# ArduSensor_Shield-v13.net
KiCad netlist of a schematic drawn in EAGLE
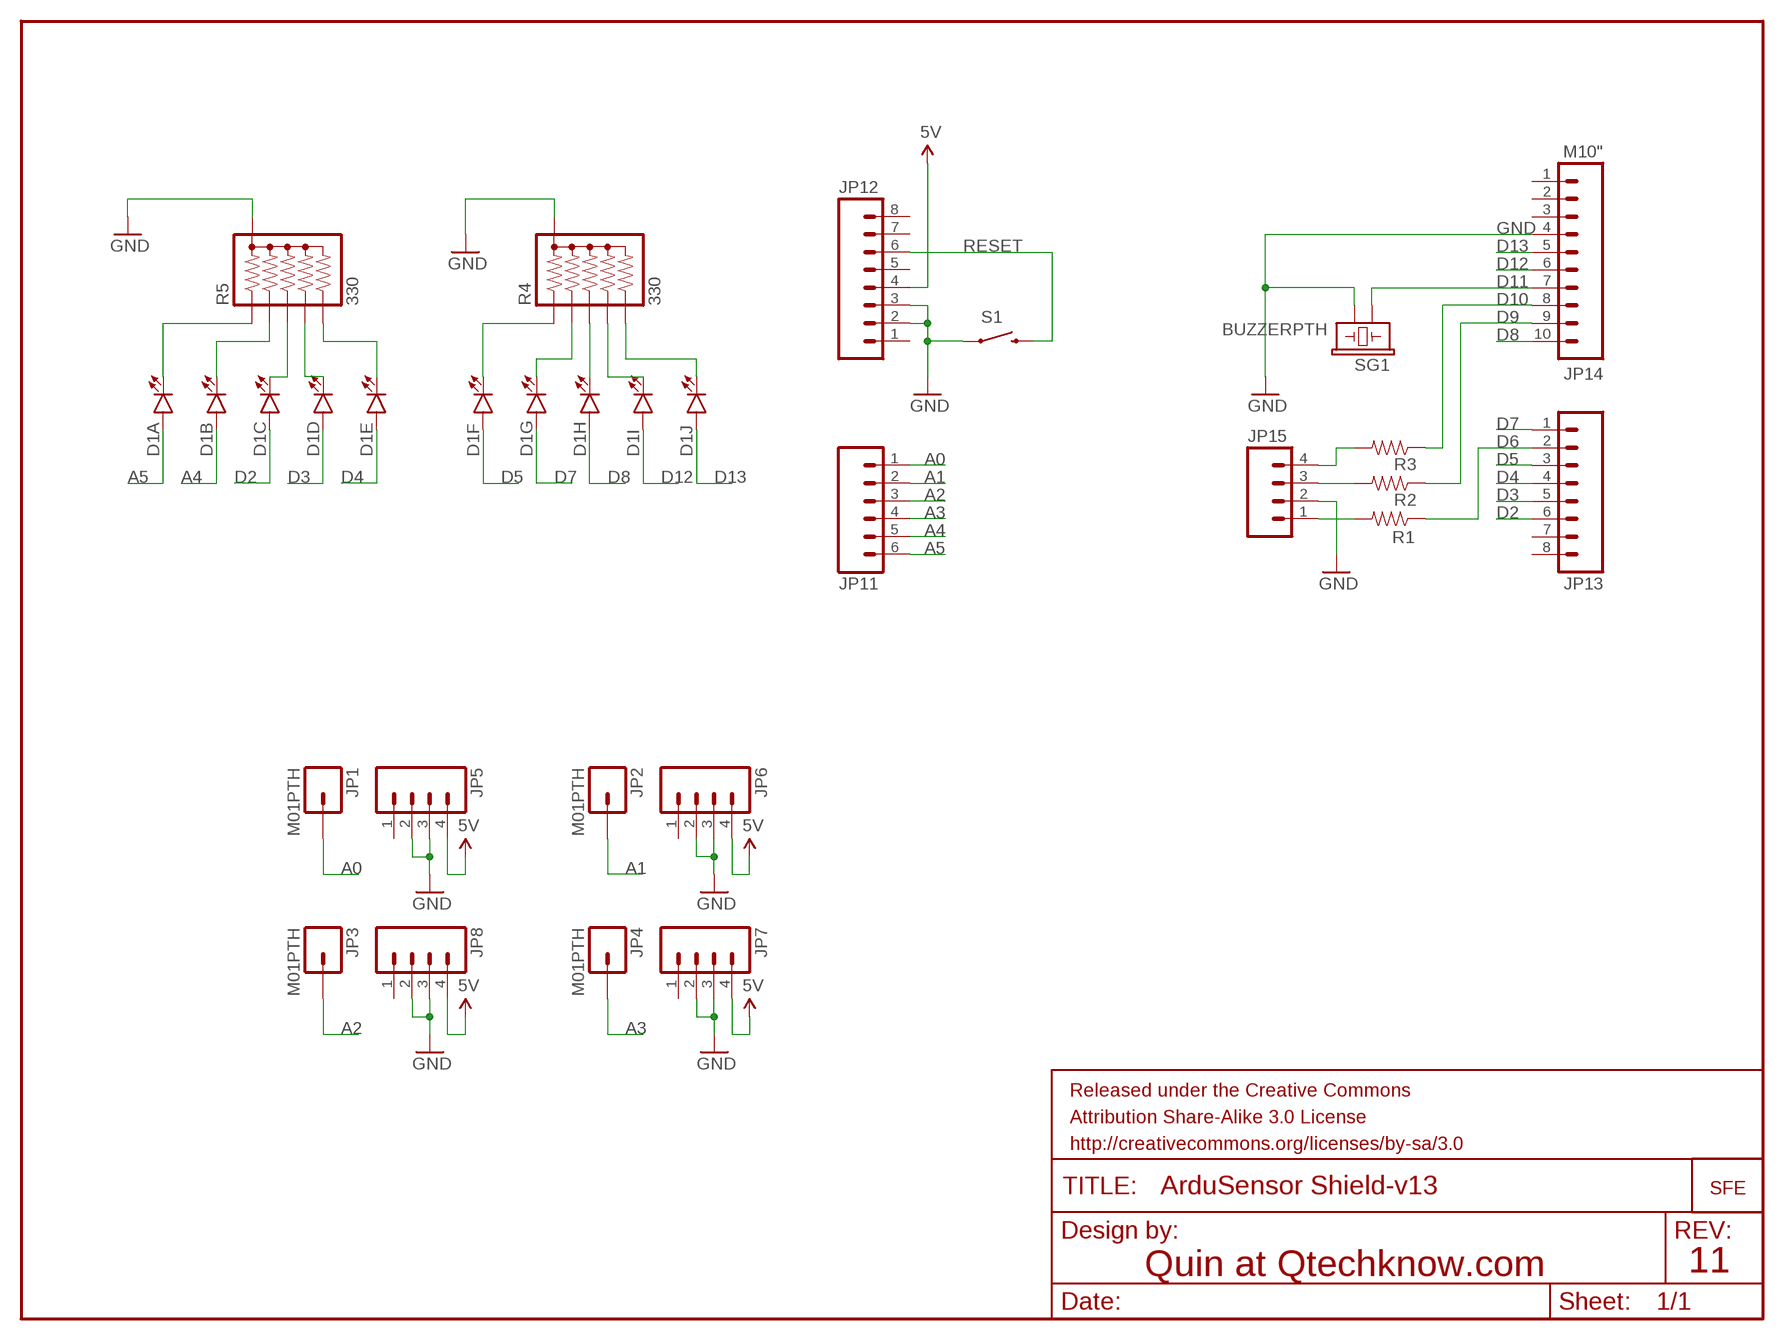
[diagram p0: schematic, sheet 1]

(export (version "E")
  (design (tool "Eeschema 10.0.6"))
  (components
    (comp (ref "D1")
      (value "LED_BARGRAPH_10")
      (footprint "eagle-import:LED_BARGAPH_10")
      (libsource (lib "eagle-import") (part "LED_BARGRAPH_10"))
    )
    (comp (ref "FRAME1")
      (value "FRAME-LETTER")
      (footprint "eagle-import:CREATIVE_COMMONS")
      (libsource (lib "eagle-import") (part "FRAME-LETTER"))
    )
    (comp (ref "JP1")
      (value "M01PTH")
      (footprint "eagle-import:1X01")
      (libsource (lib "eagle-import") (part "M01PTH"))
    )
    (comp (ref "JP2")
      (value "M01PTH")
      (footprint "eagle-import:1X01")
      (libsource (lib "eagle-import") (part "M01PTH"))
    )
    (comp (ref "JP3")
      (value "M01PTH")
      (footprint "eagle-import:1X01")
      (libsource (lib "eagle-import") (part "M01PTH"))
    )
    (comp (ref "JP4")
      (value "M01PTH")
      (footprint "eagle-import:1X01")
      (libsource (lib "eagle-import") (part "M01PTH"))
    )
    (comp (ref "JP5")
      (value "M04PTH")
      (footprint "eagle-import:1X04")
      (libsource (lib "eagle-import") (part "M04PTH"))
    )
    (comp (ref "JP6")
      (value "M04PTH")
      (footprint "eagle-import:1X04")
      (libsource (lib "eagle-import") (part "M04PTH"))
    )
    (comp (ref "JP7")
      (value "M04PTH")
      (footprint "eagle-import:1X04")
      (libsource (lib "eagle-import") (part "M04PTH"))
    )
    (comp (ref "JP8")
      (value "M04PTH")
      (footprint "eagle-import:1X04")
      (libsource (lib "eagle-import") (part "M04PTH"))
    )
    (comp (ref "JP9")
      (value "LOGO-SFENEW")
      (footprint "eagle-import:SFE-NEW-WEBLOGO")
      (libsource (lib "eagle-import") (part "LOGO-SFENEW"))
    )
    (comp (ref "JP11")
      (value "M06SIP")
      (footprint "eagle-import:1X06")
      (libsource (lib "eagle-import") (part "M06SIP"))
    )
    (comp (ref "JP12")
      (value "M081X08")
      (footprint "eagle-import:1X08")
      (libsource (lib "eagle-import") (part "M081X08"))
    )
    (comp (ref "JP13")
      (value "M081X08")
      (footprint "eagle-import:1X08")
      (libsource (lib "eagle-import") (part "M081X08"))
    )
    (comp (ref "JP14")
      (value "M10\"")
      (footprint "eagle-import:1X10")
      (libsource (lib "eagle-import") (part "M10{dblquote}"))
    )
    (comp (ref "JP15")
      (value "M04PTH")
      (footprint "eagle-import:1X04")
      (libsource (lib "eagle-import") (part "M04PTH"))
    )
    (comp (ref "R1")
      (value "RESISTORPTH-1/6W")
      (footprint "eagle-import:1_6W-RES")
      (libsource (lib "eagle-import") (part "RESISTORPTH-1/6W"))
    )
    (comp (ref "R2")
      (value "RESISTORPTH-1/6W")
      (footprint "eagle-import:1_6W-RES")
      (libsource (lib "eagle-import") (part "RESISTORPTH-1/6W"))
    )
    (comp (ref "R3")
      (value "RESISTORPTH-1/6W")
      (footprint "eagle-import:1_6W-RES")
      (libsource (lib "eagle-import") (part "RESISTORPTH-1/6W"))
    )
    (comp (ref "R4")
      (value "330")
      (footprint "eagle-import:RPACK-SIP-PTH-5")
      (libsource (lib "eagle-import") (part "RPACK-BUSSED-SIP-PTH-5"))
    )
    (comp (ref "R5")
      (value "330")
      (footprint "eagle-import:RPACK-SIP-PTH-5")
      (libsource (lib "eagle-import") (part "RPACK-BUSSED-SIP-PTH-5"))
    )
    (comp (ref "S1")
      (value "SWITCH-MOMENTARY-2PTH")
      (footprint "eagle-import:TACTILE-PTH")
      (libsource (lib "eagle-import") (part "SWITCH-MOMENTARY-2PTH"))
    )
    (comp (ref "SG1")
      (value "BUZZERPTH")
      (footprint "eagle-import:BUZZER-12MM")
      (libsource (lib "eagle-import") (part "BUZZERPTH"))
    )
  )
  (nets
    (net (code "1") (name "/A0") (class "Default")
      (node (ref "JP1") (pin "1") (pinfunction "1_1") (pintype "passive"))
      (node (ref "JP11") (pin "1") (pinfunction "1_1") (pintype "passive"))
    )
    (net (code "2") (name "/A1") (class "Default")
      (node (ref "JP11") (pin "2") (pinfunction "2_2") (pintype "passive"))
      (node (ref "JP2") (pin "1") (pinfunction "1_1") (pintype "passive"))
    )
    (net (code "3") (name "/A2") (class "Default")
      (node (ref "JP11") (pin "3") (pinfunction "3_3") (pintype "passive"))
      (node (ref "JP3") (pin "1") (pinfunction "1_1") (pintype "passive"))
    )
    (net (code "4") (name "/A3") (class "Default")
      (node (ref "JP11") (pin "4") (pinfunction "4_4") (pintype "passive"))
      (node (ref "JP4") (pin "1") (pinfunction "1_1") (pintype "passive"))
    )
    (net (code "5") (name "/A4") (class "Default")
      (node (ref "D1") (pin "2") (pinfunction "A_2") (pintype "passive"))
      (node (ref "JP11") (pin "5") (pinfunction "5_5") (pintype "passive"))
    )
    (net (code "6") (name "/A5") (class "Default")
      (node (ref "D1") (pin "1") (pinfunction "A_1") (pintype "passive"))
      (node (ref "JP11") (pin "6") (pinfunction "6_6") (pintype "passive"))
    )
    (net (code "7") (name "/D2") (class "Default")
      (node (ref "D1") (pin "3") (pinfunction "A_3") (pintype "passive"))
      (node (ref "JP13") (pin "6") (pinfunction "6_6") (pintype "passive"))
    )
    (net (code "8") (name "/D3") (class "Default")
      (node (ref "D1") (pin "4") (pinfunction "A_4") (pintype "passive"))
      (node (ref "JP13") (pin "5") (pinfunction "5_5") (pintype "passive"))
    )
    (net (code "9") (name "/D4") (class "Default")
      (node (ref "D1") (pin "5") (pinfunction "A_5") (pintype "passive"))
      (node (ref "JP13") (pin "4") (pinfunction "4_4") (pintype "passive"))
    )
    (net (code "10") (name "/D5") (class "Default")
      (node (ref "D1") (pin "6") (pinfunction "A_6") (pintype "passive"))
      (node (ref "JP13") (pin "3") (pinfunction "3_3") (pintype "passive"))
    )
    (net (code "11") (name "/D6") (class "Default")
      (node (ref "JP13") (pin "2") (pinfunction "2_2") (pintype "passive"))
      (node (ref "R1") (pin "1") (pinfunction "1_1") (pintype "passive"))
    )
    (net (code "12") (name "/D7") (class "Default")
      (node (ref "D1") (pin "7") (pinfunction "A_7") (pintype "passive"))
      (node (ref "JP13") (pin "1") (pinfunction "1_1") (pintype "passive"))
    )
    (net (code "13") (name "/D8") (class "Default")
      (node (ref "D1") (pin "8") (pinfunction "A_8") (pintype "passive"))
      (node (ref "JP14") (pin "10") (pinfunction "10_10") (pintype "passive"))
    )
    (net (code "14") (name "/D9") (class "Default")
      (node (ref "JP14") (pin "9") (pinfunction "9_9") (pintype "passive"))
      (node (ref "R2") (pin "1") (pinfunction "1_1") (pintype "passive"))
    )
    (net (code "15") (name "/D10") (class "Default")
      (node (ref "JP14") (pin "8") (pinfunction "8_8") (pintype "passive"))
      (node (ref "R3") (pin "1") (pinfunction "1_1") (pintype "passive"))
    )
    (net (code "16") (name "/D11") (class "Default")
      (node (ref "JP14") (pin "7") (pinfunction "7_7") (pintype "passive"))
      (node (ref "SG1") (pin "+") (pinfunction "1_+") (pintype "passive"))
    )
    (net (code "17") (name "/D12") (class "Default")
      (node (ref "D1") (pin "9") (pinfunction "A_9") (pintype "passive"))
      (node (ref "JP14") (pin "6") (pinfunction "6_6") (pintype "passive"))
    )
    (net (code "18") (name "/D13") (class "Default")
      (node (ref "D1") (pin "10") (pinfunction "A_10") (pintype "passive"))
      (node (ref "JP14") (pin "5") (pinfunction "5_5") (pintype "passive"))
    )
    (net (code "19") (name "/RESET") (class "Default")
      (node (ref "JP12") (pin "6") (pinfunction "6_6") (pintype "passive"))
      (node (ref "S1") (pin "3") (pinfunction "2_3") (pintype "passive"))
    )
    (net (code "20") (name "5V") (class "Default")
      (node (ref "JP12") (pin "4") (pinfunction "4_4") (pintype "passive"))
      (node (ref "JP5") (pin "4") (pinfunction "4_4") (pintype "passive"))
      (node (ref "JP6") (pin "4") (pinfunction "4_4") (pintype "passive"))
      (node (ref "JP7") (pin "4") (pinfunction "4_4") (pintype "passive"))
      (node (ref "JP8") (pin "4") (pinfunction "4_4") (pintype "passive"))
    )
    (net (code "21") (name "GND") (class "Default")
      (node (ref "JP12") (pin "2") (pinfunction "2_2") (pintype "passive"))
      (node (ref "JP12") (pin "3") (pinfunction "3_3") (pintype "passive"))
      (node (ref "JP14") (pin "4") (pinfunction "4_4") (pintype "passive"))
      (node (ref "JP15") (pin "2") (pinfunction "2_2") (pintype "passive"))
      (node (ref "JP5") (pin "2") (pinfunction "2_2") (pintype "passive"))
      (node (ref "JP5") (pin "3") (pinfunction "3_3") (pintype "passive"))
      (node (ref "JP6") (pin "2") (pinfunction "2_2") (pintype "passive"))
      (node (ref "JP6") (pin "3") (pinfunction "3_3") (pintype "passive"))
      (node (ref "JP7") (pin "2") (pinfunction "2_2") (pintype "passive"))
      (node (ref "JP7") (pin "3") (pinfunction "3_3") (pintype "passive"))
      (node (ref "JP8") (pin "2") (pinfunction "2_2") (pintype "passive"))
      (node (ref "JP8") (pin "3") (pinfunction "3_3") (pintype "passive"))
      (node (ref "R4") (pin "P$1") (pinfunction "1_P$1") (pintype "passive"))
      (node (ref "R5") (pin "P$1") (pinfunction "1_P$1") (pintype "passive"))
      (node (ref "S1") (pin "1") (pinfunction "1_1") (pintype "passive"))
      (node (ref "SG1") (pin "-") (pinfunction "2_-") (pintype "passive"))
    )
    (net (code "22") (name "Net-(D1A-C)") (class "Default")
      (node (ref "D1") (pin "20") (pinfunction "C_20") (pintype "passive"))
      (node (ref "R5") (pin "P$2") (pinfunction "2_P$2") (pintype "passive"))
    )
    (net (code "23") (name "Net-(D1B-C)") (class "Default")
      (node (ref "D1") (pin "19") (pinfunction "C_19") (pintype "passive"))
      (node (ref "R5") (pin "P$3") (pinfunction "3_P$3") (pintype "passive"))
    )
    (net (code "24") (name "Net-(D1C-C)") (class "Default")
      (node (ref "D1") (pin "18") (pinfunction "C_18") (pintype "passive"))
      (node (ref "R5") (pin "P$4") (pinfunction "4_P$4") (pintype "passive"))
    )
    (net (code "25") (name "Net-(D1D-C)") (class "Default")
      (node (ref "D1") (pin "17") (pinfunction "C_17") (pintype "passive"))
      (node (ref "R5") (pin "P$5") (pinfunction "5_P$5") (pintype "passive"))
    )
    (net (code "26") (name "Net-(D1E-C)") (class "Default")
      (node (ref "D1") (pin "16") (pinfunction "C_16") (pintype "passive"))
      (node (ref "R5") (pin "P$6") (pinfunction "6_P$6") (pintype "passive"))
    )
    (net (code "27") (name "Net-(D1F-C)") (class "Default")
      (node (ref "D1") (pin "15") (pinfunction "C_15") (pintype "passive"))
      (node (ref "R4") (pin "P$2") (pinfunction "2_P$2") (pintype "passive"))
    )
    (net (code "28") (name "Net-(D1G-C)") (class "Default")
      (node (ref "D1") (pin "14") (pinfunction "C_14") (pintype "passive"))
      (node (ref "R4") (pin "P$3") (pinfunction "3_P$3") (pintype "passive"))
    )
    (net (code "29") (name "Net-(D1H-C)") (class "Default")
      (node (ref "D1") (pin "13") (pinfunction "C_13") (pintype "passive"))
      (node (ref "R4") (pin "P$4") (pinfunction "4_P$4") (pintype "passive"))
    )
    (net (code "30") (name "Net-(D1I-C)") (class "Default")
      (node (ref "D1") (pin "12") (pinfunction "C_12") (pintype "passive"))
      (node (ref "R4") (pin "P$5") (pinfunction "5_P$5") (pintype "passive"))
    )
    (net (code "31") (name "Net-(D1J-C)") (class "Default")
      (node (ref "D1") (pin "11") (pinfunction "C_11") (pintype "passive"))
      (node (ref "R4") (pin "P$6") (pinfunction "6_P$6") (pintype "passive"))
    )
    (net (code "32") (name "Net-(JP15-Pad1)") (class "Default")
      (node (ref "JP15") (pin "1") (pinfunction "1_1") (pintype "passive"))
      (node (ref "R1") (pin "2") (pinfunction "2_2") (pintype "passive"))
    )
    (net (code "33") (name "Net-(JP15-Pad3)") (class "Default")
      (node (ref "JP15") (pin "3") (pinfunction "3_3") (pintype "passive"))
      (node (ref "R2") (pin "2") (pinfunction "2_2") (pintype "passive"))
    )
    (net (code "34") (name "Net-(JP15-Pad4)") (class "Default")
      (node (ref "JP15") (pin "4") (pinfunction "4_4") (pintype "passive"))
      (node (ref "R3") (pin "2") (pinfunction "2_2") (pintype "passive"))
    )
    (net (code "35") (name "unconnected-(JP5-Pad1)") (class "Default")
      (node (ref "JP5") (pin "1") (pinfunction "1_1") (pintype "passive"))
    )
    (net (code "36") (name "unconnected-(JP6-Pad1)") (class "Default")
      (node (ref "JP6") (pin "1") (pinfunction "1_1") (pintype "passive"))
    )
    (net (code "37") (name "unconnected-(JP7-Pad1)") (class "Default")
      (node (ref "JP7") (pin "1") (pinfunction "1_1") (pintype "passive"))
    )
    (net (code "38") (name "unconnected-(JP8-Pad1)") (class "Default")
      (node (ref "JP8") (pin "1") (pinfunction "1_1") (pintype "passive"))
    )
    (net (code "39") (name "unconnected-(JP12-Pad1)") (class "Default")
      (node (ref "JP12") (pin "1") (pinfunction "1_1") (pintype "passive"))
    )
    (net (code "40") (name "unconnected-(JP12-Pad5)") (class "Default")
      (node (ref "JP12") (pin "5") (pinfunction "5_5") (pintype "passive"))
    )
    (net (code "41") (name "unconnected-(JP12-Pad7)") (class "Default")
      (node (ref "JP12") (pin "7") (pinfunction "7_7") (pintype "passive"))
    )
    (net (code "42") (name "unconnected-(JP12-Pad8)") (class "Default")
      (node (ref "JP12") (pin "8") (pinfunction "8_8") (pintype "passive"))
    )
    (net (code "43") (name "unconnected-(JP13-Pad7)") (class "Default")
      (node (ref "JP13") (pin "7") (pinfunction "7_7") (pintype "passive"))
    )
    (net (code "44") (name "unconnected-(JP13-Pad8)") (class "Default")
      (node (ref "JP13") (pin "8") (pinfunction "8_8") (pintype "passive"))
    )
    (net (code "45") (name "unconnected-(JP14-Pad1)") (class "Default")
      (node (ref "JP14") (pin "1") (pinfunction "1_1") (pintype "passive"))
    )
    (net (code "46") (name "unconnected-(JP14-Pad2)") (class "Default")
      (node (ref "JP14") (pin "2") (pinfunction "2_2") (pintype "passive"))
    )
    (net (code "47") (name "unconnected-(JP14-Pad3)") (class "Default")
      (node (ref "JP14") (pin "3") (pinfunction "3_3") (pintype "passive"))
    )
  )
)
